# PDU_v1a.net
KiCad netlist of a schematic drawn in EAGLE
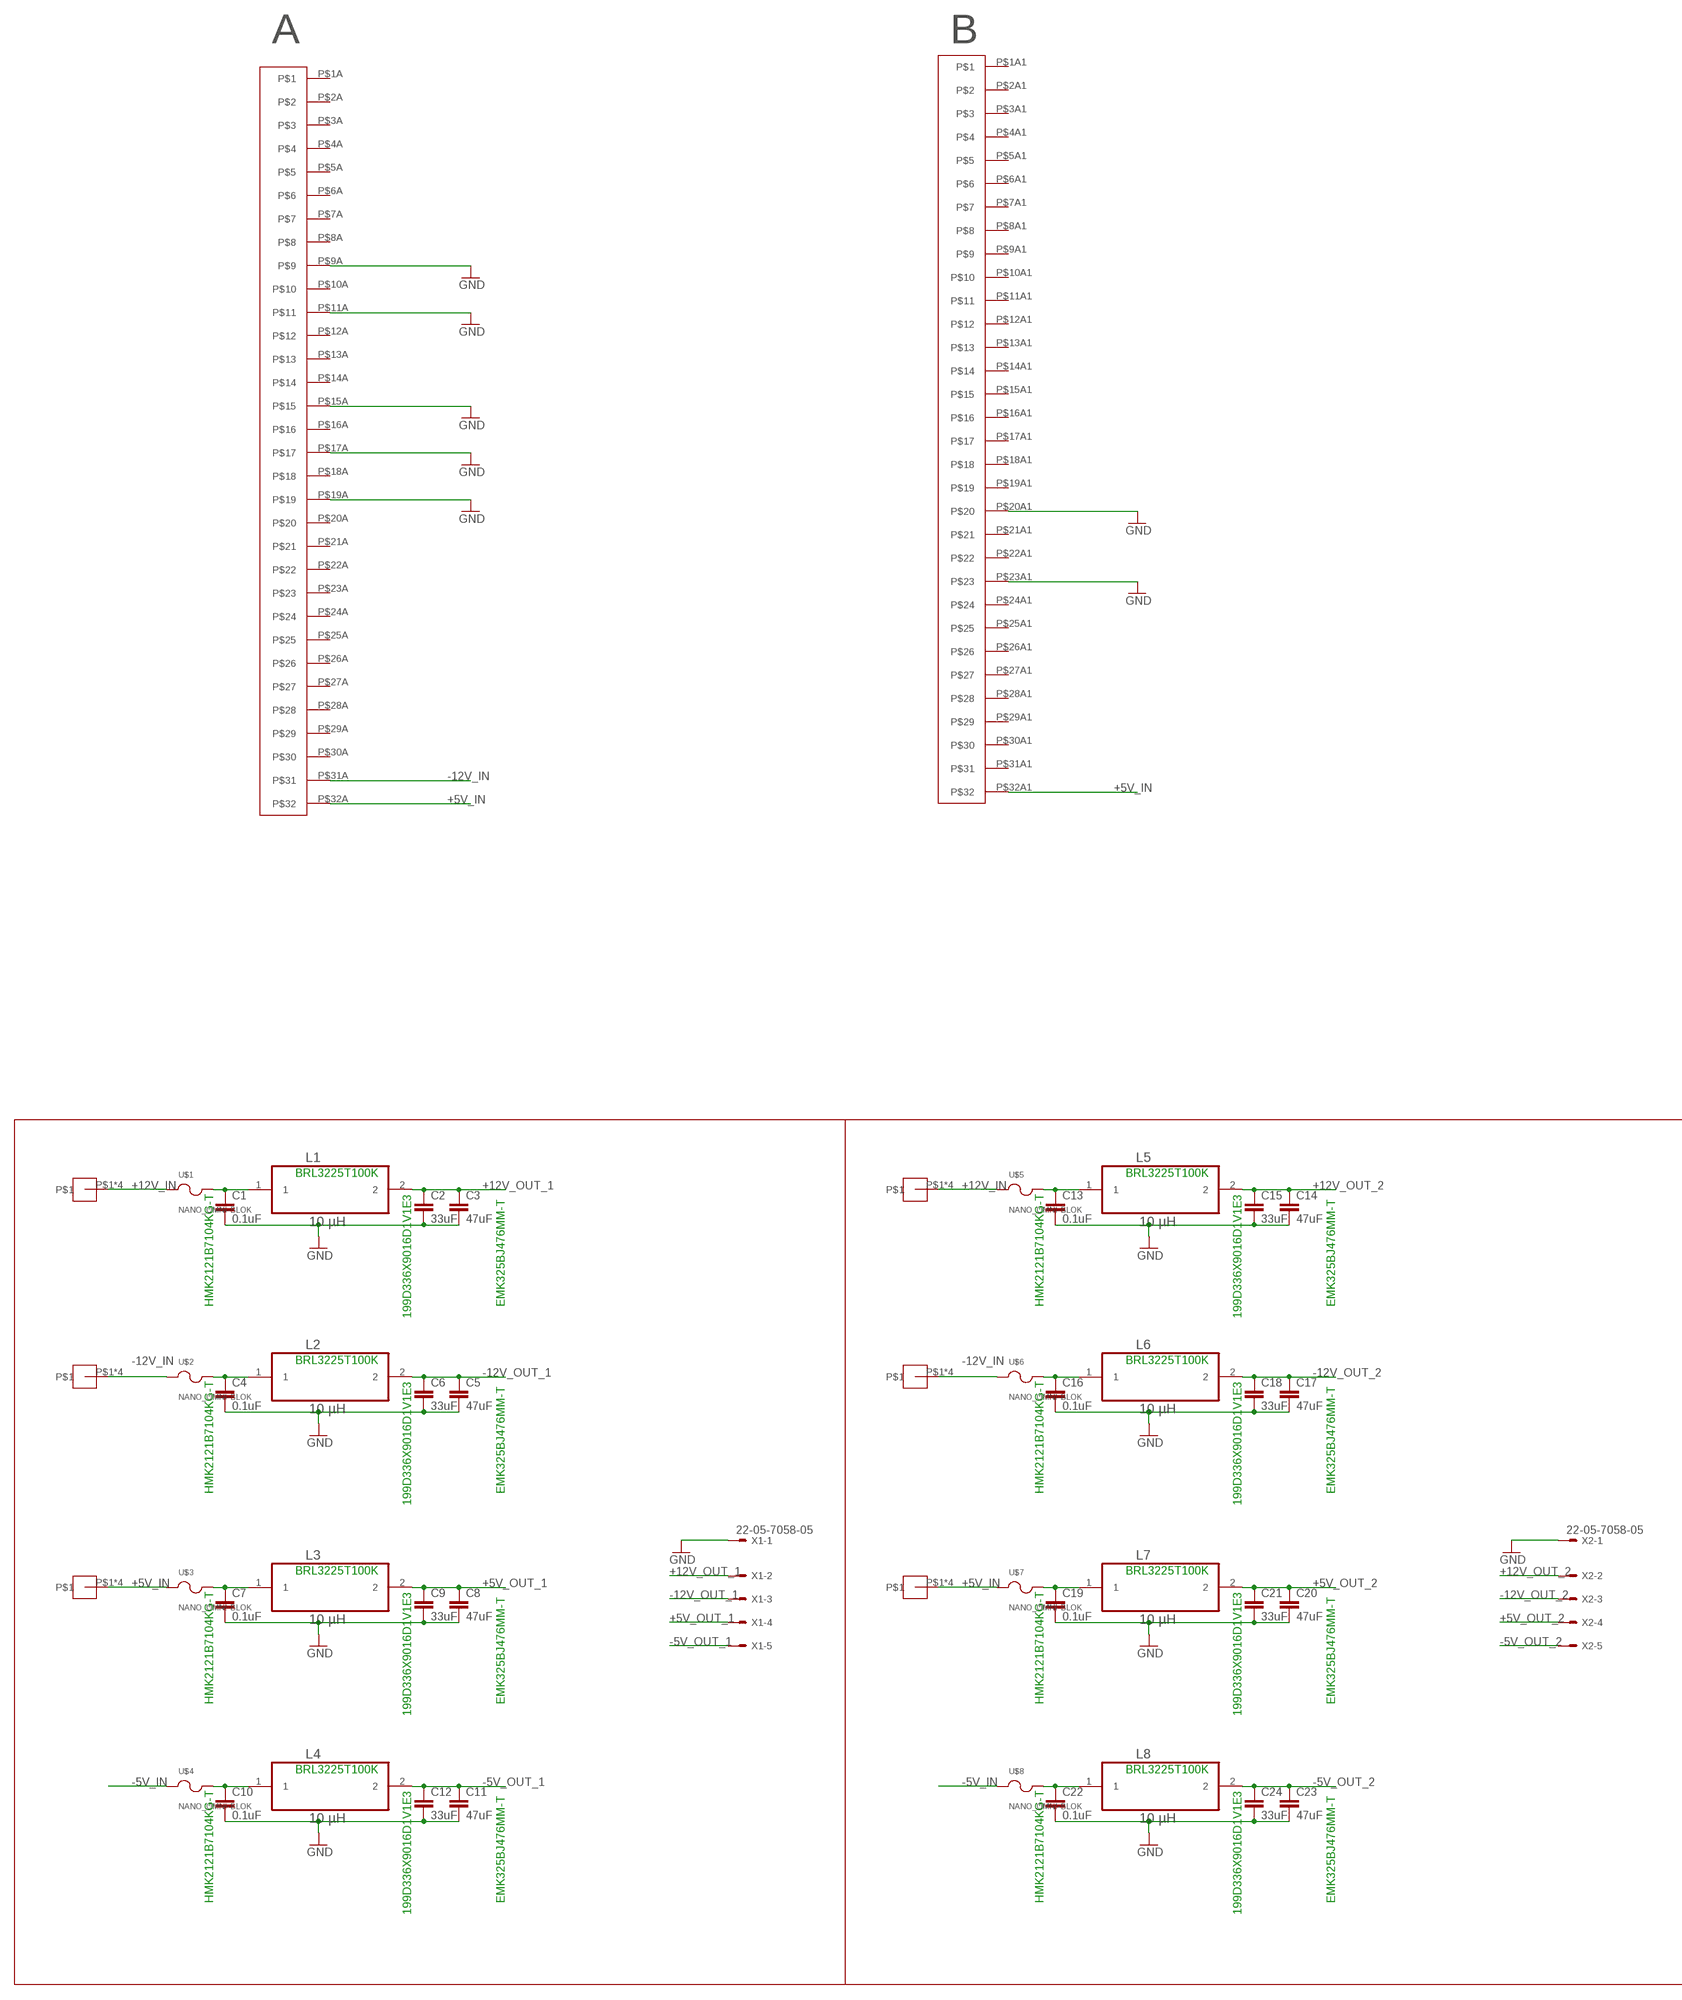
[diagram p0: schematic, sheet 1, part 1 of 2]
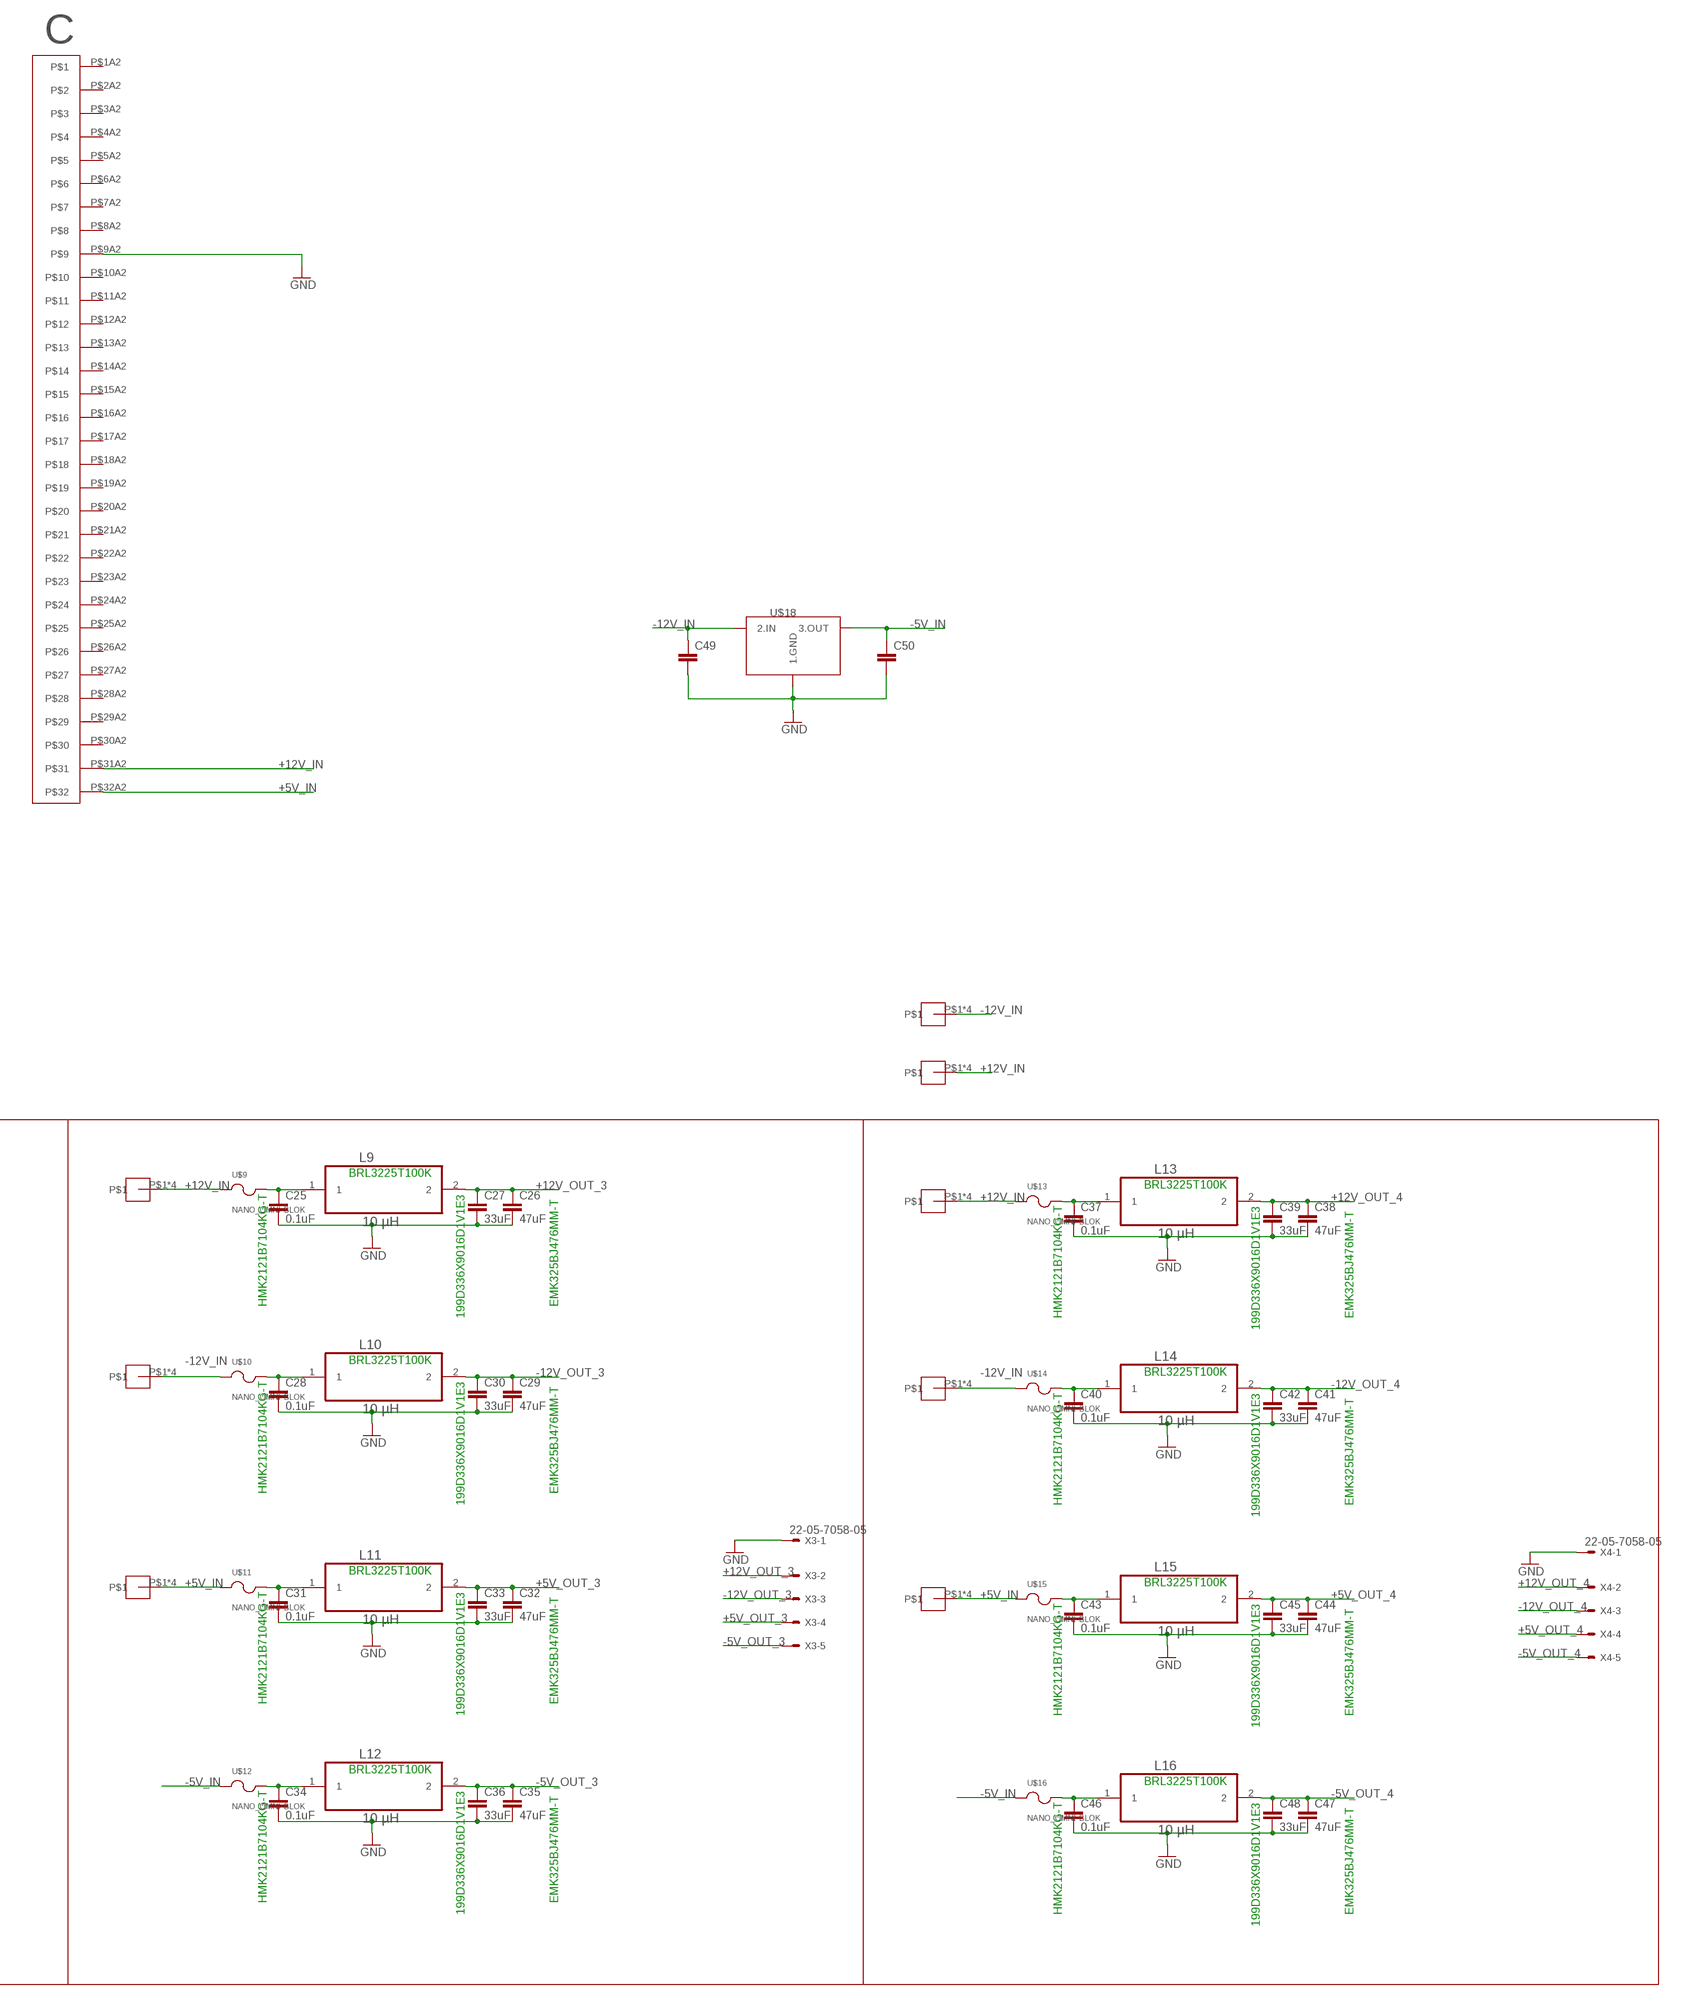
[diagram p1: schematic, sheet 1, part 2 of 2]

(export (version "E")
  (design (tool "Eeschema 10.0.6"))
  (components
    (comp (ref "+5V")
      (value "POWERTAP-7691")
      (footprint "eagle-import:KEYSTONE7691")
      (libsource (lib "eagle-import") (part "POWERTAP-7691"))
    )
    (comp (ref "+5V1")
      (value "POWERTAP-7691")
      (footprint "eagle-import:KEYSTONE7691")
      (libsource (lib "eagle-import") (part "POWERTAP-7691"))
    )
    (comp (ref "+5V2")
      (value "POWERTAP-7691")
      (footprint "eagle-import:KEYSTONE7691")
      (libsource (lib "eagle-import") (part "POWERTAP-7691"))
    )
    (comp (ref "+5V3")
      (value "POWERTAP-7691")
      (footprint "eagle-import:KEYSTONE7691")
      (libsource (lib "eagle-import") (part "POWERTAP-7691"))
    )
    (comp (ref "+12V")
      (value "POWERTAP-7691")
      (footprint "eagle-import:KEYSTONE7691")
      (libsource (lib "eagle-import") (part "POWERTAP-7691"))
    )
    (comp (ref "+12V1")
      (value "POWERTAP-7691")
      (footprint "eagle-import:KEYSTONE7691")
      (libsource (lib "eagle-import") (part "POWERTAP-7691"))
    )
    (comp (ref "+12V2")
      (value "POWERTAP-7691")
      (footprint "eagle-import:KEYSTONE7691")
      (libsource (lib "eagle-import") (part "POWERTAP-7691"))
    )
    (comp (ref "+12V3")
      (value "POWERTAP-7691")
      (footprint "eagle-import:KEYSTONE7691")
      (libsource (lib "eagle-import") (part "POWERTAP-7691"))
    )
    (comp (ref "+12V4")
      (value "POWERTAP-7691")
      (footprint "eagle-import:KEYSTONE7691")
      (libsource (lib "eagle-import") (part "POWERTAP-7691"))
    )
    (comp (ref "-12V")
      (value "POWERTAP-7691")
      (footprint "eagle-import:KEYSTONE7691")
      (libsource (lib "eagle-import") (part "POWERTAP-7691"))
    )
    (comp (ref "-12V1")
      (value "POWERTAP-7691")
      (footprint "eagle-import:KEYSTONE7691")
      (libsource (lib "eagle-import") (part "POWERTAP-7691"))
    )
    (comp (ref "-12V2")
      (value "POWERTAP-7691")
      (footprint "eagle-import:KEYSTONE7691")
      (libsource (lib "eagle-import") (part "POWERTAP-7691"))
    )
    (comp (ref "-12V3")
      (value "POWERTAP-7691")
      (footprint "eagle-import:KEYSTONE7691")
      (libsource (lib "eagle-import") (part "POWERTAP-7691"))
    )
    (comp (ref "-12V4")
      (value "POWERTAP-7691")
      (footprint "eagle-import:KEYSTONE7691")
      (libsource (lib "eagle-import") (part "POWERTAP-7691"))
    )
    (comp (ref "C1")
      (value "0.1uF")
      (footprint "eagle-import:C0805")
      (libsource (lib "eagle-import") (part "C-EUC0805"))
    )
    (comp (ref "C2")
      (value "33uF")
      (footprint "eagle-import:C025-025X050")
      (libsource (lib "eagle-import") (part "C-EU025-025X050"))
    )
    (comp (ref "C3")
      (value "47uF")
      (footprint "eagle-import:C1210")
      (libsource (lib "eagle-import") (part "C-EUC1210"))
    )
    (comp (ref "C4")
      (value "0.1uF")
      (footprint "eagle-import:C0805")
      (libsource (lib "eagle-import") (part "C-EUC0805"))
    )
    (comp (ref "C5")
      (value "47uF")
      (footprint "eagle-import:C1210")
      (libsource (lib "eagle-import") (part "C-EUC1210"))
    )
    (comp (ref "C6")
      (value "33uF")
      (footprint "eagle-import:C025-025X050")
      (libsource (lib "eagle-import") (part "C-EU025-025X050"))
    )
    (comp (ref "C7")
      (value "0.1uF")
      (footprint "eagle-import:C0805")
      (libsource (lib "eagle-import") (part "C-EUC0805"))
    )
    (comp (ref "C8")
      (value "47uF")
      (footprint "eagle-import:C1210")
      (libsource (lib "eagle-import") (part "C-EUC1210"))
    )
    (comp (ref "C9")
      (value "33uF")
      (footprint "eagle-import:C025-025X050")
      (libsource (lib "eagle-import") (part "C-EU025-025X050"))
    )
    (comp (ref "C10")
      (value "0.1uF")
      (footprint "eagle-import:C0805")
      (libsource (lib "eagle-import") (part "C-EUC0805"))
    )
    (comp (ref "C11")
      (value "47uF")
      (footprint "eagle-import:C1210")
      (libsource (lib "eagle-import") (part "C-EUC1210"))
    )
    (comp (ref "C12")
      (value "33uF")
      (footprint "eagle-import:C025-025X050")
      (libsource (lib "eagle-import") (part "C-EU025-025X050"))
    )
    (comp (ref "C13")
      (value "0.1uF")
      (footprint "eagle-import:C0805")
      (libsource (lib "eagle-import") (part "C-EUC0805"))
    )
    (comp (ref "C14")
      (value "47uF")
      (footprint "eagle-import:C1210")
      (libsource (lib "eagle-import") (part "C-EUC1210"))
    )
    (comp (ref "C15")
      (value "33uF")
      (footprint "eagle-import:C025-025X050")
      (libsource (lib "eagle-import") (part "C-EU025-025X050"))
    )
    (comp (ref "C16")
      (value "0.1uF")
      (footprint "eagle-import:C0805")
      (libsource (lib "eagle-import") (part "C-EUC0805"))
    )
    (comp (ref "C17")
      (value "47uF")
      (footprint "eagle-import:C1210")
      (libsource (lib "eagle-import") (part "C-EUC1210"))
    )
    (comp (ref "C18")
      (value "33uF")
      (footprint "eagle-import:C025-025X050")
      (libsource (lib "eagle-import") (part "C-EU025-025X050"))
    )
    (comp (ref "C19")
      (value "0.1uF")
      (footprint "eagle-import:C0805")
      (libsource (lib "eagle-import") (part "C-EUC0805"))
    )
    (comp (ref "C20")
      (value "47uF")
      (footprint "eagle-import:C1210")
      (libsource (lib "eagle-import") (part "C-EUC1210"))
    )
    (comp (ref "C21")
      (value "33uF")
      (footprint "eagle-import:C025-025X050")
      (libsource (lib "eagle-import") (part "C-EU025-025X050"))
    )
    (comp (ref "C22")
      (value "0.1uF")
      (footprint "eagle-import:C0805")
      (libsource (lib "eagle-import") (part "C-EUC0805"))
    )
    (comp (ref "C23")
      (value "47uF")
      (footprint "eagle-import:C1210")
      (libsource (lib "eagle-import") (part "C-EUC1210"))
    )
    (comp (ref "C24")
      (value "33uF")
      (footprint "eagle-import:C025-025X050")
      (libsource (lib "eagle-import") (part "C-EU025-025X050"))
    )
    (comp (ref "C25")
      (value "0.1uF")
      (footprint "eagle-import:C0805")
      (libsource (lib "eagle-import") (part "C-EUC0805"))
    )
    (comp (ref "C26")
      (value "47uF")
      (footprint "eagle-import:C1210")
      (libsource (lib "eagle-import") (part "C-EUC1210"))
    )
    (comp (ref "C27")
      (value "33uF")
      (footprint "eagle-import:C025-025X050")
      (libsource (lib "eagle-import") (part "C-EU025-025X050"))
    )
    (comp (ref "C28")
      (value "0.1uF")
      (footprint "eagle-import:C0805")
      (libsource (lib "eagle-import") (part "C-EUC0805"))
    )
    (comp (ref "C29")
      (value "47uF")
      (footprint "eagle-import:C1210")
      (libsource (lib "eagle-import") (part "C-EUC1210"))
    )
    (comp (ref "C30")
      (value "33uF")
      (footprint "eagle-import:C025-025X050")
      (libsource (lib "eagle-import") (part "C-EU025-025X050"))
    )
    (comp (ref "C31")
      (value "0.1uF")
      (footprint "eagle-import:C0805")
      (libsource (lib "eagle-import") (part "C-EUC0805"))
    )
    (comp (ref "C32")
      (value "47uF")
      (footprint "eagle-import:C1210")
      (libsource (lib "eagle-import") (part "C-EUC1210"))
    )
    (comp (ref "C33")
      (value "33uF")
      (footprint "eagle-import:C025-025X050")
      (libsource (lib "eagle-import") (part "C-EU025-025X050"))
    )
    (comp (ref "C34")
      (value "0.1uF")
      (footprint "eagle-import:C0805")
      (libsource (lib "eagle-import") (part "C-EUC0805"))
    )
    (comp (ref "C35")
      (value "47uF")
      (footprint "eagle-import:C1210")
      (libsource (lib "eagle-import") (part "C-EUC1210"))
    )
    (comp (ref "C36")
      (value "33uF")
      (footprint "eagle-import:C025-025X050")
      (libsource (lib "eagle-import") (part "C-EU025-025X050"))
    )
    (comp (ref "C37")
      (value "0.1uF")
      (footprint "eagle-import:C0805")
      (libsource (lib "eagle-import") (part "C-EUC0805"))
    )
    (comp (ref "C38")
      (value "47uF")
      (footprint "eagle-import:C1210")
      (libsource (lib "eagle-import") (part "C-EUC1210"))
    )
    (comp (ref "C39")
      (value "33uF")
      (footprint "eagle-import:C025-025X050")
      (libsource (lib "eagle-import") (part "C-EU025-025X050"))
    )
    (comp (ref "C40")
      (value "0.1uF")
      (footprint "eagle-import:C0805")
      (libsource (lib "eagle-import") (part "C-EUC0805"))
    )
    (comp (ref "C41")
      (value "47uF")
      (footprint "eagle-import:C1210")
      (libsource (lib "eagle-import") (part "C-EUC1210"))
    )
    (comp (ref "C42")
      (value "33uF")
      (footprint "eagle-import:C025-025X050")
      (libsource (lib "eagle-import") (part "C-EU025-025X050"))
    )
    (comp (ref "C43")
      (value "0.1uF")
      (footprint "eagle-import:C0805")
      (libsource (lib "eagle-import") (part "C-EUC0805"))
    )
    (comp (ref "C44")
      (value "47uF")
      (footprint "eagle-import:C1210")
      (libsource (lib "eagle-import") (part "C-EUC1210"))
    )
    (comp (ref "C45")
      (value "33uF")
      (footprint "eagle-import:C025-025X050")
      (libsource (lib "eagle-import") (part "C-EU025-025X050"))
    )
    (comp (ref "C46")
      (value "0.1uF")
      (footprint "eagle-import:C0805")
      (libsource (lib "eagle-import") (part "C-EUC0805"))
    )
    (comp (ref "C47")
      (value "47uF")
      (footprint "eagle-import:C1210")
      (libsource (lib "eagle-import") (part "C-EUC1210"))
    )
    (comp (ref "C48")
      (value "33uF")
      (footprint "eagle-import:C025-025X050")
      (libsource (lib "eagle-import") (part "C-EU025-025X050"))
    )
    (comp (ref "C49")
      (value "C-EUC0805")
      (footprint "eagle-import:C0805")
      (libsource (lib "eagle-import") (part "C-EUC0805"))
    )
    (comp (ref "C50")
      (value "C-EUC0805")
      (footprint "eagle-import:C0805")
      (libsource (lib "eagle-import") (part "C-EUC0805"))
    )
    (comp (ref "L1")
      (value "10 µH")
      (footprint "eagle-import:INDC3225X240N")
      (fields (field (name "MPN") "B82422H1333K") (field (name "TOLERANCE") "±10%"))
      (libsource (lib "eagle-import") (part "B82422H1333K"))
    )
    (comp (ref "L2")
      (value "10 µH")
      (footprint "eagle-import:INDC3225X240N")
      (fields (field (name "MPN") "B82422H1333K") (field (name "TOLERANCE") "±10%"))
      (libsource (lib "eagle-import") (part "B82422H1333K"))
    )
    (comp (ref "L3")
      (value "10 µH")
      (footprint "eagle-import:INDC3225X240N")
      (fields (field (name "MPN") "B82422H1333K") (field (name "TOLERANCE") "±10%"))
      (libsource (lib "eagle-import") (part "B82422H1333K"))
    )
    (comp (ref "L4")
      (value "10 µH")
      (footprint "eagle-import:INDC3225X240N")
      (fields (field (name "MPN") "B82422H1333K") (field (name "TOLERANCE") "±10%"))
      (libsource (lib "eagle-import") (part "B82422H1333K"))
    )
    (comp (ref "L5")
      (value "10 µH")
      (footprint "eagle-import:INDC3225X240N")
      (fields (field (name "MPN") "B82422H1333K") (field (name "TOLERANCE") "±10%"))
      (libsource (lib "eagle-import") (part "B82422H1333K"))
    )
    (comp (ref "L6")
      (value "10 µH")
      (footprint "eagle-import:INDC3225X240N")
      (fields (field (name "MPN") "B82422H1333K") (field (name "TOLERANCE") "±10%"))
      (libsource (lib "eagle-import") (part "B82422H1333K"))
    )
    (comp (ref "L7")
      (value "10 µH")
      (footprint "eagle-import:INDC3225X240N")
      (fields (field (name "MPN") "B82422H1333K") (field (name "TOLERANCE") "±10%"))
      (libsource (lib "eagle-import") (part "B82422H1333K"))
    )
    (comp (ref "L8")
      (value "10 µH")
      (footprint "eagle-import:INDC3225X240N")
      (fields (field (name "MPN") "B82422H1333K") (field (name "TOLERANCE") "±10%"))
      (libsource (lib "eagle-import") (part "B82422H1333K"))
    )
    (comp (ref "L9")
      (value "10 µH")
      (footprint "eagle-import:INDC3225X240N")
      (fields (field (name "MPN") "B82422H1333K") (field (name "TOLERANCE") "±10%"))
      (libsource (lib "eagle-import") (part "B82422H1333K"))
    )
    (comp (ref "L10")
      (value "10 µH")
      (footprint "eagle-import:INDC3225X240N")
      (fields (field (name "MPN") "B82422H1333K") (field (name "TOLERANCE") "±10%"))
      (libsource (lib "eagle-import") (part "B82422H1333K"))
    )
    (comp (ref "L11")
      (value "10 µH")
      (footprint "eagle-import:INDC3225X240N")
      (fields (field (name "MPN") "B82422H1333K") (field (name "TOLERANCE") "±10%"))
      (libsource (lib "eagle-import") (part "B82422H1333K"))
    )
    (comp (ref "L12")
      (value "10 µH")
      (footprint "eagle-import:INDC3225X240N")
      (fields (field (name "MPN") "B82422H1333K") (field (name "TOLERANCE") "±10%"))
      (libsource (lib "eagle-import") (part "B82422H1333K"))
    )
    (comp (ref "L13")
      (value "10 µH")
      (footprint "eagle-import:INDC3225X240N")
      (fields (field (name "MPN") "B82422H1333K") (field (name "TOLERANCE") "±10%"))
      (libsource (lib "eagle-import") (part "B82422H1333K"))
    )
    (comp (ref "L14")
      (value "10 µH")
      (footprint "eagle-import:INDC3225X240N")
      (fields (field (name "MPN") "B82422H1333K") (field (name "TOLERANCE") "±10%"))
      (libsource (lib "eagle-import") (part "B82422H1333K"))
    )
    (comp (ref "L15")
      (value "10 µH")
      (footprint "eagle-import:INDC3225X240N")
      (fields (field (name "MPN") "B82422H1333K") (field (name "TOLERANCE") "±10%"))
      (libsource (lib "eagle-import") (part "B82422H1333K"))
    )
    (comp (ref "L16")
      (value "10 µH")
      (footprint "eagle-import:INDC3225X240N")
      (fields (field (name "MPN") "B82422H1333K") (field (name "TOLERANCE") "±10%"))
      (libsource (lib "eagle-import") (part "B82422H1333K"))
    )
    (comp (ref "U$1")
      (value "NANO_OMNI-BLOK")
      (footprint "eagle-import:NANO2-OMNI-BLOK")
      (libsource (lib "eagle-import") (part "NANO_OMNI-BLOK"))
    )
    (comp (ref "U$2")
      (value "NANO_OMNI-BLOK")
      (footprint "eagle-import:NANO2-OMNI-BLOK")
      (libsource (lib "eagle-import") (part "NANO_OMNI-BLOK"))
    )
    (comp (ref "U$3")
      (value "NANO_OMNI-BLOK")
      (footprint "eagle-import:NANO2-OMNI-BLOK")
      (libsource (lib "eagle-import") (part "NANO_OMNI-BLOK"))
    )
    (comp (ref "U$4")
      (value "NANO_OMNI-BLOK")
      (footprint "eagle-import:NANO2-OMNI-BLOK")
      (libsource (lib "eagle-import") (part "NANO_OMNI-BLOK"))
    )
    (comp (ref "U$5")
      (value "NANO_OMNI-BLOK")
      (footprint "eagle-import:NANO2-OMNI-BLOK")
      (libsource (lib "eagle-import") (part "NANO_OMNI-BLOK"))
    )
    (comp (ref "U$6")
      (value "NANO_OMNI-BLOK")
      (footprint "eagle-import:NANO2-OMNI-BLOK")
      (libsource (lib "eagle-import") (part "NANO_OMNI-BLOK"))
    )
    (comp (ref "U$7")
      (value "NANO_OMNI-BLOK")
      (footprint "eagle-import:NANO2-OMNI-BLOK")
      (libsource (lib "eagle-import") (part "NANO_OMNI-BLOK"))
    )
    (comp (ref "U$8")
      (value "NANO_OMNI-BLOK")
      (footprint "eagle-import:NANO2-OMNI-BLOK")
      (libsource (lib "eagle-import") (part "NANO_OMNI-BLOK"))
    )
    (comp (ref "U$9")
      (value "NANO_OMNI-BLOK")
      (footprint "eagle-import:NANO2-OMNI-BLOK")
      (libsource (lib "eagle-import") (part "NANO_OMNI-BLOK"))
    )
    (comp (ref "U$10")
      (value "NANO_OMNI-BLOK")
      (footprint "eagle-import:NANO2-OMNI-BLOK")
      (libsource (lib "eagle-import") (part "NANO_OMNI-BLOK"))
    )
    (comp (ref "U$11")
      (value "NANO_OMNI-BLOK")
      (footprint "eagle-import:NANO2-OMNI-BLOK")
      (libsource (lib "eagle-import") (part "NANO_OMNI-BLOK"))
    )
    (comp (ref "U$12")
      (value "NANO_OMNI-BLOK")
      (footprint "eagle-import:NANO2-OMNI-BLOK")
      (libsource (lib "eagle-import") (part "NANO_OMNI-BLOK"))
    )
    (comp (ref "U$13")
      (value "NANO_OMNI-BLOK")
      (footprint "eagle-import:NANO2-OMNI-BLOK")
      (libsource (lib "eagle-import") (part "NANO_OMNI-BLOK"))
    )
    (comp (ref "U$14")
      (value "NANO_OMNI-BLOK")
      (footprint "eagle-import:NANO2-OMNI-BLOK")
      (libsource (lib "eagle-import") (part "NANO_OMNI-BLOK"))
    )
    (comp (ref "U$15")
      (value "NANO_OMNI-BLOK")
      (footprint "eagle-import:NANO2-OMNI-BLOK")
      (libsource (lib "eagle-import") (part "NANO_OMNI-BLOK"))
    )
    (comp (ref "U$16")
      (value "NANO_OMNI-BLOK")
      (footprint "eagle-import:NANO2-OMNI-BLOK")
      (libsource (lib "eagle-import") (part "NANO_OMNI-BLOK"))
    )
    (comp (ref "U$17")
      (value "DIN_41612_PLUG")
      (footprint "eagle-import:DIN_41612_PLUG")
      (libsource (lib "eagle-import") (part "DIN_41612_PLUG"))
    )
    (comp (ref "U$18")
      (value "LM2990")
      (footprint "eagle-import:TO-263-3")
      (libsource (lib "eagle-import") (part "LM2990"))
    )
    (comp (ref "X1")
      (value "22-05-7058-05")
      (footprint "eagle-import:7395-05")
      (libsource (lib "eagle-import") (part "22-?-0505-7058"))
    )
    (comp (ref "X2")
      (value "22-05-7058-05")
      (footprint "eagle-import:7395-05")
      (libsource (lib "eagle-import") (part "22-?-0505-7058"))
    )
    (comp (ref "X3")
      (value "22-05-7058-05")
      (footprint "eagle-import:7395-05")
      (libsource (lib "eagle-import") (part "22-?-0505-7058"))
    )
    (comp (ref "X4")
      (value "22-05-7058-05")
      (footprint "eagle-import:7395-05")
      (libsource (lib "eagle-import") (part "22-?-0505-7058"))
    )
  )
  (nets
    (net (code "1") (name "+5V_IN") (class "Default")
      (node (ref "+5V") (pin "P$1") (pinfunction "P$1_P$1") (pintype "bidirectional"))
      (node (ref "+5V") (pin "P$2") (pinfunction "P$1_P$2") (pintype "bidirectional"))
      (node (ref "+5V") (pin "P$3") (pinfunction "P$1_P$3") (pintype "bidirectional"))
      (node (ref "+5V") (pin "P$4") (pinfunction "P$1_P$4") (pintype "bidirectional"))
      (node (ref "+5V1") (pin "P$1") (pinfunction "P$1_P$1") (pintype "bidirectional"))
      (node (ref "+5V1") (pin "P$2") (pinfunction "P$1_P$2") (pintype "bidirectional"))
      (node (ref "+5V1") (pin "P$3") (pinfunction "P$1_P$3") (pintype "bidirectional"))
      (node (ref "+5V1") (pin "P$4") (pinfunction "P$1_P$4") (pintype "bidirectional"))
      (node (ref "+5V2") (pin "P$1") (pinfunction "P$1_P$1") (pintype "bidirectional"))
      (node (ref "+5V2") (pin "P$2") (pinfunction "P$1_P$2") (pintype "bidirectional"))
      (node (ref "+5V2") (pin "P$3") (pinfunction "P$1_P$3") (pintype "bidirectional"))
      (node (ref "+5V2") (pin "P$4") (pinfunction "P$1_P$4") (pintype "bidirectional"))
      (node (ref "+5V3") (pin "P$1") (pinfunction "P$1_P$1") (pintype "bidirectional"))
      (node (ref "+5V3") (pin "P$2") (pinfunction "P$1_P$2") (pintype "bidirectional"))
      (node (ref "+5V3") (pin "P$3") (pinfunction "P$1_P$3") (pintype "bidirectional"))
      (node (ref "+5V3") (pin "P$4") (pinfunction "P$1_P$4") (pintype "bidirectional"))
      (node (ref "U$11") (pin "P$1") (pinfunction "P$1_P$1") (pintype "bidirectional"))
      (node (ref "U$15") (pin "P$1") (pinfunction "P$1_P$1") (pintype "bidirectional"))
      (node (ref "U$17") (pin "P$32A") (pinfunction "P$32_P$32A") (pintype "bidirectional"))
      (node (ref "U$17") (pin "P$32A1") (pinfunction "P$32_P$32A1") (pintype "bidirectional"))
      (node (ref "U$17") (pin "P$32A2") (pinfunction "P$32_P$32A2") (pintype "bidirectional"))
      (node (ref "U$3") (pin "P$1") (pinfunction "P$1_P$1") (pintype "bidirectional"))
      (node (ref "U$7") (pin "P$1") (pinfunction "P$1_P$1") (pintype "bidirectional"))
    )
    (net (code "2") (name "+5V_OUT_1") (class "Default")
      (node (ref "C8") (pin "1") (pinfunction "1_1") (pintype "passive"))
      (node (ref "C9") (pin "1") (pinfunction "1_1") (pintype "passive"))
      (node (ref "L3") (pin "2") (pinfunction "2_2") (pintype "passive"))
      (node (ref "X1") (pin "4") (pinfunction "S_4") (pintype "passive"))
    )
    (net (code "3") (name "+5V_OUT_2") (class "Default")
      (node (ref "C20") (pin "1") (pinfunction "1_1") (pintype "passive"))
      (node (ref "C21") (pin "1") (pinfunction "1_1") (pintype "passive"))
      (node (ref "L7") (pin "2") (pinfunction "2_2") (pintype "passive"))
      (node (ref "X2") (pin "4") (pinfunction "S_4") (pintype "passive"))
    )
    (net (code "4") (name "+5V_OUT_3") (class "Default")
      (node (ref "C32") (pin "1") (pinfunction "1_1") (pintype "passive"))
      (node (ref "C33") (pin "1") (pinfunction "1_1") (pintype "passive"))
      (node (ref "L11") (pin "2") (pinfunction "2_2") (pintype "passive"))
      (node (ref "X3") (pin "4") (pinfunction "S_4") (pintype "passive"))
    )
    (net (code "5") (name "+5V_OUT_4") (class "Default")
      (node (ref "C44") (pin "1") (pinfunction "1_1") (pintype "passive"))
      (node (ref "C45") (pin "1") (pinfunction "1_1") (pintype "passive"))
      (node (ref "L15") (pin "2") (pinfunction "2_2") (pintype "passive"))
      (node (ref "X4") (pin "4") (pinfunction "S_4") (pintype "passive"))
    )
    (net (code "6") (name "+12V_IN") (class "Default")
      (node (ref "+12V") (pin "P$1") (pinfunction "P$1_P$1") (pintype "bidirectional"))
      (node (ref "+12V") (pin "P$2") (pinfunction "P$1_P$2") (pintype "bidirectional"))
      (node (ref "+12V") (pin "P$3") (pinfunction "P$1_P$3") (pintype "bidirectional"))
      (node (ref "+12V") (pin "P$4") (pinfunction "P$1_P$4") (pintype "bidirectional"))
      (node (ref "+12V1") (pin "P$1") (pinfunction "P$1_P$1") (pintype "bidirectional"))
      (node (ref "+12V1") (pin "P$2") (pinfunction "P$1_P$2") (pintype "bidirectional"))
      (node (ref "+12V1") (pin "P$3") (pinfunction "P$1_P$3") (pintype "bidirectional"))
      (node (ref "+12V1") (pin "P$4") (pinfunction "P$1_P$4") (pintype "bidirectional"))
      (node (ref "+12V2") (pin "P$1") (pinfunction "P$1_P$1") (pintype "bidirectional"))
      (node (ref "+12V2") (pin "P$2") (pinfunction "P$1_P$2") (pintype "bidirectional"))
      (node (ref "+12V2") (pin "P$3") (pinfunction "P$1_P$3") (pintype "bidirectional"))
      (node (ref "+12V2") (pin "P$4") (pinfunction "P$1_P$4") (pintype "bidirectional"))
      (node (ref "+12V3") (pin "P$1") (pinfunction "P$1_P$1") (pintype "bidirectional"))
      (node (ref "+12V3") (pin "P$2") (pinfunction "P$1_P$2") (pintype "bidirectional"))
      (node (ref "+12V3") (pin "P$3") (pinfunction "P$1_P$3") (pintype "bidirectional"))
      (node (ref "+12V3") (pin "P$4") (pinfunction "P$1_P$4") (pintype "bidirectional"))
      (node (ref "+12V4") (pin "P$1") (pinfunction "P$1_P$1") (pintype "bidirectional"))
      (node (ref "+12V4") (pin "P$2") (pinfunction "P$1_P$2") (pintype "bidirectional"))
      (node (ref "+12V4") (pin "P$3") (pinfunction "P$1_P$3") (pintype "bidirectional"))
      (node (ref "+12V4") (pin "P$4") (pinfunction "P$1_P$4") (pintype "bidirectional"))
      (node (ref "U$1") (pin "P$1") (pinfunction "P$1_P$1") (pintype "bidirectional"))
      (node (ref "U$13") (pin "P$1") (pinfunction "P$1_P$1") (pintype "bidirectional"))
      (node (ref "U$17") (pin "P$31A2") (pinfunction "P$31_P$31A2") (pintype "bidirectional"))
      (node (ref "U$5") (pin "P$1") (pinfunction "P$1_P$1") (pintype "bidirectional"))
      (node (ref "U$9") (pin "P$1") (pinfunction "P$1_P$1") (pintype "bidirectional"))
    )
    (net (code "7") (name "+12V_OUT_1") (class "Default")
      (node (ref "C2") (pin "1") (pinfunction "1_1") (pintype "passive"))
      (node (ref "C3") (pin "1") (pinfunction "1_1") (pintype "passive"))
      (node (ref "L1") (pin "2") (pinfunction "2_2") (pintype "passive"))
      (node (ref "X1") (pin "2") (pinfunction "S_2") (pintype "passive"))
    )
    (net (code "8") (name "+12V_OUT_2") (class "Default")
      (node (ref "C14") (pin "1") (pinfunction "1_1") (pintype "passive"))
      (node (ref "C15") (pin "1") (pinfunction "1_1") (pintype "passive"))
      (node (ref "L5") (pin "2") (pinfunction "2_2") (pintype "passive"))
      (node (ref "X2") (pin "2") (pinfunction "S_2") (pintype "passive"))
    )
    (net (code "9") (name "+12V_OUT_3") (class "Default")
      (node (ref "C26") (pin "1") (pinfunction "1_1") (pintype "passive"))
      (node (ref "C27") (pin "1") (pinfunction "1_1") (pintype "passive"))
      (node (ref "L9") (pin "2") (pinfunction "2_2") (pintype "passive"))
      (node (ref "X3") (pin "2") (pinfunction "S_2") (pintype "passive"))
    )
    (net (code "10") (name "+12V_OUT_4") (class "Default")
      (node (ref "C38") (pin "1") (pinfunction "1_1") (pintype "passive"))
      (node (ref "C39") (pin "1") (pinfunction "1_1") (pintype "passive"))
      (node (ref "L13") (pin "2") (pinfunction "2_2") (pintype "passive"))
      (node (ref "X4") (pin "2") (pinfunction "S_2") (pintype "passive"))
    )
    (net (code "11") (name "-5V_IN") (class "Default")
      (node (ref "C50") (pin "1") (pinfunction "1_1") (pintype "passive"))
      (node (ref "U$12") (pin "P$1") (pinfunction "P$1_P$1") (pintype "bidirectional"))
      (node (ref "U$16") (pin "P$1") (pinfunction "P$1_P$1") (pintype "bidirectional"))
      (node (ref "U$18") (pin "P$3") (pinfunction "3.OUT_P$3") (pintype "bidirectional"))
      (node (ref "U$4") (pin "P$1") (pinfunction "P$1_P$1") (pintype "bidirectional"))
      (node (ref "U$8") (pin "P$1") (pinfunction "P$1_P$1") (pintype "bidirectional"))
    )
    (net (code "12") (name "-5V_OUT_1") (class "Default")
      (node (ref "C11") (pin "1") (pinfunction "1_1") (pintype "passive"))
      (node (ref "C12") (pin "1") (pinfunction "1_1") (pintype "passive"))
      (node (ref "L4") (pin "2") (pinfunction "2_2") (pintype "passive"))
      (node (ref "X1") (pin "5") (pinfunction "S_5") (pintype "passive"))
    )
    (net (code "13") (name "-5V_OUT_2") (class "Default")
      (node (ref "C23") (pin "1") (pinfunction "1_1") (pintype "passive"))
      (node (ref "C24") (pin "1") (pinfunction "1_1") (pintype "passive"))
      (node (ref "L8") (pin "2") (pinfunction "2_2") (pintype "passive"))
      (node (ref "X2") (pin "5") (pinfunction "S_5") (pintype "passive"))
    )
    (net (code "14") (name "-5V_OUT_3") (class "Default")
      (node (ref "C35") (pin "1") (pinfunction "1_1") (pintype "passive"))
      (node (ref "C36") (pin "1") (pinfunction "1_1") (pintype "passive"))
      (node (ref "L12") (pin "2") (pinfunction "2_2") (pintype "passive"))
      (node (ref "X3") (pin "5") (pinfunction "S_5") (pintype "passive"))
    )
    (net (code "15") (name "-5V_OUT_4") (class "Default")
      (node (ref "C47") (pin "1") (pinfunction "1_1") (pintype "passive"))
      (node (ref "C48") (pin "1") (pinfunction "1_1") (pintype "passive"))
      (node (ref "L16") (pin "2") (pinfunction "2_2") (pintype "passive"))
      (node (ref "X4") (pin "5") (pinfunction "S_5") (pintype "passive"))
    )
    (net (code "16") (name "-12V_IN") (class "Default")
      (node (ref "-12V") (pin "P$1") (pinfunction "P$1_P$1") (pintype "bidirectional"))
      (node (ref "-12V") (pin "P$2") (pinfunction "P$1_P$2") (pintype "bidirectional"))
      (node (ref "-12V") (pin "P$3") (pinfunction "P$1_P$3") (pintype "bidirectional"))
      (node (ref "-12V") (pin "P$4") (pinfunction "P$1_P$4") (pintype "bidirectional"))
      (node (ref "-12V1") (pin "P$1") (pinfunction "P$1_P$1") (pintype "bidirectional"))
      (node (ref "-12V1") (pin "P$2") (pinfunction "P$1_P$2") (pintype "bidirectional"))
      (node (ref "-12V1") (pin "P$3") (pinfunction "P$1_P$3") (pintype "bidirectional"))
      (node (ref "-12V1") (pin "P$4") (pinfunction "P$1_P$4") (pintype "bidirectional"))
      (node (ref "-12V2") (pin "P$1") (pinfunction "P$1_P$1") (pintype "bidirectional"))
      (node (ref "-12V2") (pin "P$2") (pinfunction "P$1_P$2") (pintype "bidirectional"))
      (node (ref "-12V2") (pin "P$3") (pinfunction "P$1_P$3") (pintype "bidirectional"))
      (node (ref "-12V2") (pin "P$4") (pinfunction "P$1_P$4") (pintype "bidirectional"))
      (node (ref "-12V3") (pin "P$1") (pinfunction "P$1_P$1") (pintype "bidirectional"))
      (node (ref "-12V3") (pin "P$2") (pinfunction "P$1_P$2") (pintype "bidirectional"))
      (node (ref "-12V3") (pin "P$3") (pinfunction "P$1_P$3") (pintype "bidirectional"))
      (node (ref "-12V3") (pin "P$4") (pinfunction "P$1_P$4") (pintype "bidirectional"))
      (node (ref "-12V4") (pin "P$1") (pinfunction "P$1_P$1") (pintype "bidirectional"))
      (node (ref "-12V4") (pin "P$2") (pinfunction "P$1_P$2") (pintype "bidirectional"))
      (node (ref "-12V4") (pin "P$3") (pinfunction "P$1_P$3") (pintype "bidirectional"))
      (node (ref "-12V4") (pin "P$4") (pinfunction "P$1_P$4") (pintype "bidirectional"))
      (node (ref "C49") (pin "1") (pinfunction "1_1") (pintype "passive"))
      (node (ref "U$10") (pin "P$1") (pinfunction "P$1_P$1") (pintype "bidirectional"))
      (node (ref "U$14") (pin "P$1") (pinfunction "P$1_P$1") (pintype "bidirectional"))
      (node (ref "U$17") (pin "P$31A") (pinfunction "P$31_P$31A") (pintype "bidirectional"))
      (node (ref "U$18") (pin "P$2") (pinfunction "2.IN_P$2") (pintype "bidirectional"))
      (node (ref "U$18") (pin "P$4") (pinfunction "2.IN_P$4") (pintype "bidirectional"))
      (node (ref "U$2") (pin "P$1") (pinfunction "P$1_P$1") (pintype "bidirectional"))
      (node (ref "U$6") (pin "P$1") (pinfunction "P$1_P$1") (pintype "bidirectional"))
    )
    (net (code "17") (name "-12V_OUT_1") (class "Default")
      (node (ref "C5") (pin "1") (pinfunction "1_1") (pintype "passive"))
      (node (ref "C6") (pin "1") (pinfunction "1_1") (pintype "passive"))
      (node (ref "L2") (pin "2") (pinfunction "2_2") (pintype "passive"))
      (node (ref "X1") (pin "3") (pinfunction "S_3") (pintype "passive"))
    )
    (net (code "18") (name "-12V_OUT_2") (class "Default")
      (node (ref "C17") (pin "1") (pinfunction "1_1") (pintype "passive"))
      (node (ref "C18") (pin "1") (pinfunction "1_1") (pintype "passive"))
      (node (ref "L6") (pin "2") (pinfunction "2_2") (pintype "passive"))
      (node (ref "X2") (pin "3") (pinfunction "S_3") (pintype "passive"))
    )
    (net (code "19") (name "-12V_OUT_3") (class "Default")
      (node (ref "C29") (pin "1") (pinfunction "1_1") (pintype "passive"))
      (node (ref "C30") (pin "1") (pinfunction "1_1") (pintype "passive"))
      (node (ref "L10") (pin "2") (pinfunction "2_2") (pintype "passive"))
      (node (ref "X3") (pin "3") (pinfunction "S_3") (pintype "passive"))
    )
    (net (code "20") (name "-12V_OUT_4") (class "Default")
      (node (ref "C41") (pin "1") (pinfunction "1_1") (pintype "passive"))
      (node (ref "C42") (pin "1") (pinfunction "1_1") (pintype "passive"))
      (node (ref "L14") (pin "2") (pinfunction "2_2") (pintype "passive"))
      (node (ref "X4") (pin "3") (pinfunction "S_3") (pintype "passive"))
    )
    (net (code "21") (name "GND") (class "Default")
      (node (ref "C1") (pin "2") (pinfunction "2_2") (pintype "passive"))
      (node (ref "C10") (pin "2") (pinfunction "2_2") (pintype "passive"))
      (node (ref "C11") (pin "2") (pinfunction "2_2") (pintype "passive"))
      (node (ref "C12") (pin "2") (pinfunction "2_2") (pintype "passive"))
      (node (ref "C13") (pin "2") (pinfunction "2_2") (pintype "passive"))
      (node (ref "C14") (pin "2") (pinfunction "2_2") (pintype "passive"))
      (node (ref "C15") (pin "2") (pinfunction "2_2") (pintype "passive"))
      (node (ref "C16") (pin "2") (pinfunction "2_2") (pintype "passive"))
      (node (ref "C17") (pin "2") (pinfunction "2_2") (pintype "passive"))
      (node (ref "C18") (pin "2") (pinfunction "2_2") (pintype "passive"))
      (node (ref "C19") (pin "2") (pinfunction "2_2") (pintype "passive"))
      (node (ref "C2") (pin "2") (pinfunction "2_2") (pintype "passive"))
      (node (ref "C20") (pin "2") (pinfunction "2_2") (pintype "passive"))
      (node (ref "C21") (pin "2") (pinfunction "2_2") (pintype "passive"))
      (node (ref "C22") (pin "2") (pinfunction "2_2") (pintype "passive"))
      (node (ref "C23") (pin "2") (pinfunction "2_2") (pintype "passive"))
      (node (ref "C24") (pin "2") (pinfunction "2_2") (pintype "passive"))
      (node (ref "C25") (pin "2") (pinfunction "2_2") (pintype "passive"))
      (node (ref "C26") (pin "2") (pinfunction "2_2") (pintype "passive"))
      (node (ref "C27") (pin "2") (pinfunction "2_2") (pintype "passive"))
      (node (ref "C28") (pin "2") (pinfunction "2_2") (pintype "passive"))
      (node (ref "C29") (pin "2") (pinfunction "2_2") (pintype "passive"))
      (node (ref "C3") (pin "2") (pinfunction "2_2") (pintype "passive"))
      (node (ref "C30") (pin "2") (pinfunction "2_2") (pintype "passive"))
      (node (ref "C31") (pin "2") (pinfunction "2_2") (pintype "passive"))
      (node (ref "C32") (pin "2") (pinfunction "2_2") (pintype "passive"))
      (node (ref "C33") (pin "2") (pinfunction "2_2") (pintype "passive"))
      (node (ref "C34") (pin "2") (pinfunction "2_2") (pintype "passive"))
      (node (ref "C35") (pin "2") (pinfunction "2_2") (pintype "passive"))
      (node (ref "C36") (pin "2") (pinfunction "2_2") (pintype "passive"))
      (node (ref "C37") (pin "2") (pinfunction "2_2") (pintype "passive"))
      (node (ref "C38") (pin "2") (pinfunction "2_2") (pintype "passive"))
      (node (ref "C39") (pin "2") (pinfunction "2_2") (pintype "passive"))
      (node (ref "C4") (pin "2") (pinfunction "2_2") (pintype "passive"))
      (node (ref "C40") (pin "2") (pinfunction "2_2") (pintype "passive"))
      (node (ref "C41") (pin "2") (pinfunction "2_2") (pintype "passive"))
      (node (ref "C42") (pin "2") (pinfunction "2_2") (pintype "passive"))
      (node (ref "C43") (pin "2") (pinfunction "2_2") (pintype "passive"))
      (node (ref "C44") (pin "2") (pinfunction "2_2") (pintype "passive"))
      (node (ref "C45") (pin "2") (pinfunction "2_2") (pintype "passive"))
      (node (ref "C46") (pin "2") (pinfunction "2_2") (pintype "passive"))
      (node (ref "C47") (pin "2") (pinfunction "2_2") (pintype "passive"))
      (node (ref "C48") (pin "2") (pinfunction "2_2") (pintype "passive"))
      (node (ref "C49") (pin "2") (pinfunction "2_2") (pintype "passive"))
      (node (ref "C5") (pin "2") (pinfunction "2_2") (pintype "passive"))
      (node (ref "C50") (pin "2") (pinfunction "2_2") (pintype "passive"))
      (node (ref "C6") (pin "2") (pinfunction "2_2") (pintype "passive"))
      (node (ref "C7") (pin "2") (pinfunction "2_2") (pintype "passive"))
      (node (ref "C8") (pin "2") (pinfunction "2_2") (pintype "passive"))
      (node (ref "C9") (pin "2") (pinfunction "2_2") (pintype "passive"))
      (node (ref "U$17") (pin "P$11A") (pinfunction "P$11_P$11A") (pintype "bidirectional"))
      (node (ref "U$17") (pin "P$15A") (pinfunction "P$15_P$15A") (pintype "bidirectional"))
      (node (ref "U$17") (pin "P$17A") (pinfunction "P$17_P$17A") (pintype "bidirectional"))
      (node (ref "U$17") (pin "P$19A") (pinfunction "P$19_P$19A") (pintype "bidirectional"))
      (node (ref "U$17") (pin "P$20A1") (pinfunction "P$20_P$20A1") (pintype "bidirectional"))
      (node (ref "U$17") (pin "P$23A1") (pinfunction "P$23_P$23A1") (pintype "bidirectional"))
      (node (ref "U$17") (pin "P$9A") (pinfunction "P$9_P$9A") (pintype "bidirectional"))
      (node (ref "U$17") (pin "P$9A2") (pinfunction "P$9_P$9A2") (pintype "bidirectional"))
      (node (ref "U$18") (pin "P$1") (pinfunction "1.GND_P$1") (pintype "bidirectional"))
      (node (ref "X1") (pin "1") (pinfunction "S_1") (pintype "passive"))
      (node (ref "X2") (pin "1") (pinfunction "S_1") (pintype "passive"))
      (node (ref "X3") (pin "1") (pinfunction "S_1") (pintype "passive"))
      (node (ref "X4") (pin "1") (pinfunction "S_1") (pintype "passive"))
    )
    (net (code "22") (name "Net-(C1-Pad1)") (class "Default")
      (node (ref "C1") (pin "1") (pinfunction "1_1") (pintype "passive"))
      (node (ref "L1") (pin "1") (pinfunction "1_1") (pintype "passive"))
      (node (ref "U$1") (pin "P$2") (pinfunction "P$2_P$2") (pintype "bidirectional"))
    )
    (net (code "23") (name "Net-(C4-Pad1)") (class "Default")
      (node (ref "C4") (pin "1") (pinfunction "1_1") (pintype "passive"))
      (node (ref "L2") (pin "1") (pinfunction "1_1") (pintype "passive"))
      (node (ref "U$2") (pin "P$2") (pinfunction "P$2_P$2") (pintype "bidirectional"))
    )
    (net (code "24") (name "Net-(C7-Pad1)") (class "Default")
      (node (ref "C7") (pin "1") (pinfunction "1_1") (pintype "passive"))
      (node (ref "L3") (pin "1") (pinfunction "1_1") (pintype "passive"))
      (node (ref "U$3") (pin "P$2") (pinfunction "P$2_P$2") (pintype "bidirectional"))
    )
    (net (code "25") (name "Net-(C10-Pad1)") (class "Default")
      (node (ref "C10") (pin "1") (pinfunction "1_1") (pintype "passive"))
      (node (ref "L4") (pin "1") (pinfunction "1_1") (pintype "passive"))
      (node (ref "U$4") (pin "P$2") (pinfunction "P$2_P$2") (pintype "bidirectional"))
    )
    (net (code "26") (name "Net-(C13-Pad1)") (class "Default")
      (node (ref "C13") (pin "1") (pinfunction "1_1") (pintype "passive"))
      (node (ref "L5") (pin "1") (pinfunction "1_1") (pintype "passive"))
      (node (ref "U$5") (pin "P$2") (pinfunction "P$2_P$2") (pintype "bidirectional"))
    )
    (net (code "27") (name "Net-(C16-Pad1)") (class "Default")
      (node (ref "C16") (pin "1") (pinfunction "1_1") (pintype "passive"))
      (node (ref "L6") (pin "1") (pinfunction "1_1") (pintype "passive"))
      (node (ref "U$6") (pin "P$2") (pinfunction "P$2_P$2") (pintype "bidirectional"))
    )
    (net (code "28") (name "Net-(C19-Pad1)") (class "Default")
      (node (ref "C19") (pin "1") (pinfunction "1_1") (pintype "passive"))
      (node (ref "L7") (pin "1") (pinfunction "1_1") (pintype "passive"))
      (node (ref "U$7") (pin "P$2") (pinfunction "P$2_P$2") (pintype "bidirectional"))
    )
    (net (code "29") (name "Net-(C22-Pad1)") (class "Default")
      (node (ref "C22") (pin "1") (pinfunction "1_1") (pintype "passive"))
      (node (ref "L8") (pin "1") (pinfunction "1_1") (pintype "passive"))
      (node (ref "U$8") (pin "P$2") (pinfunction "P$2_P$2") (pintype "bidirectional"))
    )
    (net (code "30") (name "Net-(C25-Pad1)") (class "Default")
      (node (ref "C25") (pin "1") (pinfunction "1_1") (pintype "passive"))
      (node (ref "L9") (pin "1") (pinfunction "1_1") (pintype "passive"))
      (node (ref "U$9") (pin "P$2") (pinfunction "P$2_P$2") (pintype "bidirectional"))
    )
    (net (code "31") (name "Net-(C28-Pad1)") (class "Default")
      (node (ref "C28") (pin "1") (pinfunction "1_1") (pintype "passive"))
      (node (ref "L10") (pin "1") (pinfunction "1_1") (pintype "passive"))
      (node (ref "U$10") (pin "P$2") (pinfunction "P$2_P$2") (pintype "bidirectional"))
    )
    (net (code "32") (name "Net-(C31-Pad1)") (class "Default")
      (node (ref "C31") (pin "1") (pinfunction "1_1") (pintype "passive"))
      (node (ref "L11") (pin "1") (pinfunction "1_1") (pintype "passive"))
      (node (ref "U$11") (pin "P$2") (pinfunction "P$2_P$2") (pintype "bidirectional"))
    )
    (net (code "33") (name "Net-(C34-Pad1)") (class "Default")
      (node (ref "C34") (pin "1") (pinfunction "1_1") (pintype "passive"))
      (node (ref "L12") (pin "1") (pinfunction "1_1") (pintype "passive"))
      (node (ref "U$12") (pin "P$2") (pinfunction "P$2_P$2") (pintype "bidirectional"))
    )
    (net (code "34") (name "Net-(C37-Pad1)") (class "Default")
      (node (ref "C37") (pin "1") (pinfunction "1_1") (pintype "passive"))
      (node (ref "L13") (pin "1") (pinfunction "1_1") (pintype "passive"))
      (node (ref "U$13") (pin "P$2") (pinfunction "P$2_P$2") (pintype "bidirectional"))
    )
    (net (code "35") (name "Net-(C40-Pad1)") (class "Default")
      (node (ref "C40") (pin "1") (pinfunction "1_1") (pintype "passive"))
      (node (ref "L14") (pin "1") (pinfunction "1_1") (pintype "passive"))
      (node (ref "U$14") (pin "P$2") (pinfunction "P$2_P$2") (pintype "bidirectional"))
    )
    (net (code "36") (name "Net-(C43-Pad1)") (class "Default")
      (node (ref "C43") (pin "1") (pinfunction "1_1") (pintype "passive"))
      (node (ref "L15") (pin "1") (pinfunction "1_1") (pintype "passive"))
      (node (ref "U$15") (pin "P$2") (pinfunction "P$2_P$2") (pintype "bidirectional"))
    )
    (net (code "37") (name "Net-(C46-Pad1)") (class "Default")
      (node (ref "C46") (pin "1") (pinfunction "1_1") (pintype "passive"))
      (node (ref "L16") (pin "1") (pinfunction "1_1") (pintype "passive"))
      (node (ref "U$16") (pin "P$2") (pinfunction "P$2_P$2") (pintype "bidirectional"))
    )
    (net (code "38") (name "unconnected-(U$17A-P$1-PadP$1A)") (class "Default")
      (node (ref "U$17") (pin "P$1A") (pinfunction "P$1_P$1A") (pintype "bidirectional"))
    )
    (net (code "39") (name "unconnected-(U$17A-P$2-PadP$2A)") (class "Default")
      (node (ref "U$17") (pin "P$2A") (pinfunction "P$2_P$2A") (pintype "bidirectional"))
    )
    (net (code "40") (name "unconnected-(U$17A-P$3-PadP$3A)") (class "Default")
      (node (ref "U$17") (pin "P$3A") (pinfunction "P$3_P$3A") (pintype "bidirectional"))
    )
    (net (code "41") (name "unconnected-(U$17A-P$4-PadP$4A)") (class "Default")
      (node (ref "U$17") (pin "P$4A") (pinfunction "P$4_P$4A") (pintype "bidirectional"))
    )
    (net (code "42") (name "unconnected-(U$17A-P$5-PadP$5A)") (class "Default")
      (node (ref "U$17") (pin "P$5A") (pinfunction "P$5_P$5A") (pintype "bidirectional"))
    )
    (net (code "43") (name "unconnected-(U$17A-P$6-PadP$6A)") (class "Default")
      (node (ref "U$17") (pin "P$6A") (pinfunction "P$6_P$6A") (pintype "bidirectional"))
    )
    (net (code "44") (name "unconnected-(U$17A-P$7-PadP$7A)") (class "Default")
      (node (ref "U$17") (pin "P$7A") (pinfunction "P$7_P$7A") (pintype "bidirectional"))
    )
    (net (code "45") (name "unconnected-(U$17A-P$8-PadP$8A)") (class "Default")
      (node (ref "U$17") (pin "P$8A") (pinfunction "P$8_P$8A") (pintype "bidirectional"))
    )
    (net (code "46") (name "unconnected-(U$17A-P$10-PadP$10A)") (class "Default")
      (node (ref "U$17") (pin "P$10A") (pinfunction "P$10_P$10A") (pintype "bidirectional"))
    )
    (net (code "47") (name "unconnected-(U$17A-P$12-PadP$12A)") (class "Default")
      (node (ref "U$17") (pin "P$12A") (pinfunction "P$12_P$12A") (pintype "bidirectional"))
    )
    (net (code "48") (name "unconnected-(U$17A-P$13-PadP$13A)") (class "Default")
      (node (ref "U$17") (pin "P$13A") (pinfunction "P$13_P$13A") (pintype "bidirectional"))
    )
    (net (code "49") (name "unconnected-(U$17A-P$14-PadP$14A)") (class "Default")
      (node (ref "U$17") (pin "P$14A") (pinfunction "P$14_P$14A") (pintype "bidirectional"))
    )
    (net (code "50") (name "unconnected-(U$17A-P$16-PadP$16A)") (class "Default")
      (node (ref "U$17") (pin "P$16A") (pinfunction "P$16_P$16A") (pintype "bidirectional"))
    )
    (net (code "51") (name "unconnected-(U$17A-P$18-PadP$18A)") (class "Default")
      (node (ref "U$17") (pin "P$18A") (pinfunction "P$18_P$18A") (pintype "bidirectional"))
    )
    (net (code "52") (name "unconnected-(U$17A-P$20-PadP$20A)") (class "Default")
      (node (ref "U$17") (pin "P$20A") (pinfunction "P$20_P$20A") (pintype "bidirectional"))
    )
    (net (code "53") (name "unconnected-(U$17A-P$21-PadP$21A)") (class "Default")
      (node (ref "U$17") (pin "P$21A") (pinfunction "P$21_P$21A") (pintype "bidirectional"))
    )
    (net (code "54") (name "unconnected-(U$17A-P$22-PadP$22A)") (class "Default")
      (node (ref "U$17") (pin "P$22A") (pinfunction "P$22_P$22A") (pintype "bidirectional"))
    )
    (net (code "55") (name "unconnected-(U$17A-P$23-PadP$23A)") (class "Default")
      (node (ref "U$17") (pin "P$23A") (pinfunction "P$23_P$23A") (pintype "bidirectional"))
    )
    (net (code "56") (name "unconnected-(U$17A-P$24-PadP$24A)") (class "Default")
      (node (ref "U$17") (pin "P$24A") (pinfunction "P$24_P$24A") (pintype "bidirectional"))
    )
    (net (code "57") (name "unconnected-(U$17A-P$25-PadP$25A)") (class "Default")
      (node (ref "U$17") (pin "P$25A") (pinfunction "P$25_P$25A") (pintype "bidirectional"))
    )
    (net (code "58") (name "unconnected-(U$17A-P$26-PadP$26A)") (class "Default")
      (node (ref "U$17") (pin "P$26A") (pinfunction "P$26_P$26A") (pintype "bidirectional"))
    )
    (net (code "59") (name "unconnected-(U$17A-P$27-PadP$27A)") (class "Default")
      (node (ref "U$17") (pin "P$27A") (pinfunction "P$27_P$27A") (pintype "bidirectional"))
    )
    (net (code "60") (name "unconnected-(U$17A-P$28-PadP$28A)") (class "Default")
      (node (ref "U$17") (pin "P$28A") (pinfunction "P$28_P$28A") (pintype "bidirectional"))
    )
    (net (code "61") (name "unconnected-(U$17A-P$29-PadP$29A)") (class "Default")
      (node (ref "U$17") (pin "P$29A") (pinfunction "P$29_P$29A") (pintype "bidirectional"))
    )
    (net (code "62") (name "unconnected-(U$17A-P$30-PadP$30A)") (class "Default")
      (node (ref "U$17") (pin "P$30A") (pinfunction "P$30_P$30A") (pintype "bidirectional"))
    )
    (net (code "63") (name "unconnected-(U$17B-P$1-PadP$1A1)") (class "Default")
      (node (ref "U$17") (pin "P$1A1") (pinfunction "P$1_P$1A1") (pintype "bidirectional"))
    )
    (net (code "64") (name "unconnected-(U$17B-P$2-PadP$2A1)") (class "Default")
      (node (ref "U$17") (pin "P$2A1") (pinfunction "P$2_P$2A1") (pintype "bidirectional"))
    )
    (net (code "65") (name "unconnected-(U$17B-P$3-PadP$3A1)") (class "Default")
      (node (ref "U$17") (pin "P$3A1") (pinfunction "P$3_P$3A1") (pintype "bidirectional"))
    )
    (net (code "66") (name "unconnected-(U$17B-P$4-PadP$4A1)") (class "Default")
      (node (ref "U$17") (pin "P$4A1") (pinfunction "P$4_P$4A1") (pintype "bidirectional"))
    )
    (net (code "67") (name "unconnected-(U$17B-P$5-PadP$5A1)") (class "Default")
      (node (ref "U$17") (pin "P$5A1") (pinfunction "P$5_P$5A1") (pintype "bidirectional"))
    )
    (net (code "68") (name "unconnected-(U$17B-P$6-PadP$6A1)") (class "Default")
      (node (ref "U$17") (pin "P$6A1") (pinfunction "P$6_P$6A1") (pintype "bidirectional"))
    )
    (net (code "69") (name "unconnected-(U$17B-P$7-PadP$7A1)") (class "Default")
      (node (ref "U$17") (pin "P$7A1") (pinfunction "P$7_P$7A1") (pintype "bidirectional"))
    )
    (net (code "70") (name "unconnected-(U$17B-P$8-PadP$8A1)") (class "Default")
      (node (ref "U$17") (pin "P$8A1") (pinfunction "P$8_P$8A1") (pintype "bidirectional"))
    )
    (net (code "71") (name "unconnected-(U$17B-P$9-PadP$9A1)") (class "Default")
      (node (ref "U$17") (pin "P$9A1") (pinfunction "P$9_P$9A1") (pintype "bidirectional"))
    )
    (net (code "72") (name "unconnected-(U$17B-P$10-PadP$10A1)") (class "Default")
      (node (ref "U$17") (pin "P$10A1") (pinfunction "P$10_P$10A1") (pintype "bidirectional"))
    )
    (net (code "73") (name "unconnected-(U$17B-P$11-PadP$11A1)") (class "Default")
      (node (ref "U$17") (pin "P$11A1") (pinfunction "P$11_P$11A1") (pintype "bidirectional"))
    )
    (net (code "74") (name "unconnected-(U$17B-P$12-PadP$12A1)") (class "Default")
      (node (ref "U$17") (pin "P$12A1") (pinfunction "P$12_P$12A1") (pintype "bidirectional"))
    )
    (net (code "75") (name "unconnected-(U$17B-P$13-PadP$13A1)") (class "Default")
      (node (ref "U$17") (pin "P$13A1") (pinfunction "P$13_P$13A1") (pintype "bidirectional"))
    )
    (net (code "76") (name "unconnected-(U$17B-P$14-PadP$14A1)") (class "Default")
      (node (ref "U$17") (pin "P$14A1") (pinfunction "P$14_P$14A1") (pintype "bidirectional"))
    )
    (net (code "77") (name "unconnected-(U$17B-P$15-PadP$15A1)") (class "Default")
      (node (ref "U$17") (pin "P$15A1") (pinfunction "P$15_P$15A1") (pintype "bidirectional"))
    )
    (net (code "78") (name "unconnected-(U$17B-P$16-PadP$16A1)") (class "Default")
      (node (ref "U$17") (pin "P$16A1") (pinfunction "P$16_P$16A1") (pintype "bidirectional"))
    )
    (net (code "79") (name "unconnected-(U$17B-P$17-PadP$17A1)") (class "Default")
      (node (ref "U$17") (pin "P$17A1") (pinfunction "P$17_P$17A1") (pintype "bidirectional"))
    )
    (net (code "80") (name "unconnected-(U$17B-P$18-PadP$18A1)") (class "Default")
      (node (ref "U$17") (pin "P$18A1") (pinfunction "P$18_P$18A1") (pintype "bidirectional"))
    )
    (net (code "81") (name "unconnected-(U$17B-P$19-PadP$19A1)") (class "Default")
      (node (ref "U$17") (pin "P$19A1") (pinfunction "P$19_P$19A1") (pintype "bidirectional"))
    )
    (net (code "82") (name "unconnected-(U$17B-P$21-PadP$21A1)") (class "Default")
      (node (ref "U$17") (pin "P$21A1") (pinfunction "P$21_P$21A1") (pintype "bidirectional"))
    )
    (net (code "83") (name "unconnected-(U$17B-P$22-PadP$22A1)") (class "Default")
      (node (ref "U$17") (pin "P$22A1") (pinfunction "P$22_P$22A1") (pintype "bidirectional"))
    )
    (net (code "84") (name "unconnected-(U$17B-P$24-PadP$24A1)") (class "Default")
      (node (ref "U$17") (pin "P$24A1") (pinfunction "P$24_P$24A1") (pintype "bidirectional"))
    )
    (net (code "85") (name "unconnected-(U$17B-P$25-PadP$25A1)") (class "Default")
      (node (ref "U$17") (pin "P$25A1") (pinfunction "P$25_P$25A1") (pintype "bidirectional"))
    )
    (net (code "86") (name "unconnected-(U$17B-P$26-PadP$26A1)") (class "Default")
      (node (ref "U$17") (pin "P$26A1") (pinfunction "P$26_P$26A1") (pintype "bidirectional"))
    )
    (net (code "87") (name "unconnected-(U$17B-P$27-PadP$27A1)") (class "Default")
      (node (ref "U$17") (pin "P$27A1") (pinfunction "P$27_P$27A1") (pintype "bidirectional"))
    )
    (net (code "88") (name "unconnected-(U$17B-P$28-PadP$28A1)") (class "Default")
      (node (ref "U$17") (pin "P$28A1") (pinfunction "P$28_P$28A1") (pintype "bidirectional"))
    )
    (net (code "89") (name "unconnected-(U$17B-P$29-PadP$29A1)") (class "Default")
      (node (ref "U$17") (pin "P$29A1") (pinfunction "P$29_P$29A1") (pintype "bidirectional"))
    )
    (net (code "90") (name "unconnected-(U$17B-P$30-PadP$30A1)") (class "Default")
      (node (ref "U$17") (pin "P$30A1") (pinfunction "P$30_P$30A1") (pintype "bidirectional"))
    )
    (net (code "91") (name "unconnected-(U$17B-P$31-PadP$31A1)") (class "Default")
      (node (ref "U$17") (pin "P$31A1") (pinfunction "P$31_P$31A1") (pintype "bidirectional"))
    )
    (net (code "92") (name "unconnected-(U$17C-P$1-PadP$1A2)") (class "Default")
      (node (ref "U$17") (pin "P$1A2") (pinfunction "P$1_P$1A2") (pintype "bidirectional"))
    )
    (net (code "93") (name "unconnected-(U$17C-P$2-PadP$2A2)") (class "Default")
      (node (ref "U$17") (pin "P$2A2") (pinfunction "P$2_P$2A2") (pintype "bidirectional"))
    )
    (net (code "94") (name "unconnected-(U$17C-P$3-PadP$3A2)") (class "Default")
      (node (ref "U$17") (pin "P$3A2") (pinfunction "P$3_P$3A2") (pintype "bidirectional"))
    )
    (net (code "95") (name "unconnected-(U$17C-P$4-PadP$4A2)") (class "Default")
      (node (ref "U$17") (pin "P$4A2") (pinfunction "P$4_P$4A2") (pintype "bidirectional"))
    )
    (net (code "96") (name "unconnected-(U$17C-P$5-PadP$5A2)") (class "Default")
      (node (ref "U$17") (pin "P$5A2") (pinfunction "P$5_P$5A2") (pintype "bidirectional"))
    )
    (net (code "97") (name "unconnected-(U$17C-P$6-PadP$6A2)") (class "Default")
      (node (ref "U$17") (pin "P$6A2") (pinfunction "P$6_P$6A2") (pintype "bidirectional"))
    )
    (net (code "98") (name "unconnected-(U$17C-P$7-PadP$7A2)") (class "Default")
      (node (ref "U$17") (pin "P$7A2") (pinfunction "P$7_P$7A2") (pintype "bidirectional"))
    )
    (net (code "99") (name "unconnected-(U$17C-P$8-PadP$8A2)") (class "Default")
      (node (ref "U$17") (pin "P$8A2") (pinfunction "P$8_P$8A2") (pintype "bidirectional"))
    )
    (net (code "100") (name "unconnected-(U$17C-P$10-PadP$10A2)") (class "Default")
      (node (ref "U$17") (pin "P$10A2") (pinfunction "P$10_P$10A2") (pintype "bidirectional"))
    )
    (net (code "101") (name "unconnected-(U$17C-P$11-PadP$11A2)") (class "Default")
      (node (ref "U$17") (pin "P$11A2") (pinfunction "P$11_P$11A2") (pintype "bidirectional"))
    )
    (net (code "102") (name "unconnected-(U$17C-P$12-PadP$12A2)") (class "Default")
      (node (ref "U$17") (pin "P$12A2") (pinfunction "P$12_P$12A2") (pintype "bidirectional"))
    )
    (net (code "103") (name "unconnected-(U$17C-P$13-PadP$13A2)") (class "Default")
      (node (ref "U$17") (pin "P$13A2") (pinfunction "P$13_P$13A2") (pintype "bidirectional"))
    )
    (net (code "104") (name "unconnected-(U$17C-P$14-PadP$14A2)") (class "Default")
      (node (ref "U$17") (pin "P$14A2") (pinfunction "P$14_P$14A2") (pintype "bidirectional"))
    )
    (net (code "105") (name "unconnected-(U$17C-P$15-PadP$15A2)") (class "Default")
      (node (ref "U$17") (pin "P$15A2") (pinfunction "P$15_P$15A2") (pintype "bidirectional"))
    )
    (net (code "106") (name "unconnected-(U$17C-P$16-PadP$16A2)") (class "Default")
      (node (ref "U$17") (pin "P$16A2") (pinfunction "P$16_P$16A2") (pintype "bidirectional"))
    )
    (net (code "107") (name "unconnected-(U$17C-P$17-PadP$17A2)") (class "Default")
      (node (ref "U$17") (pin "P$17A2") (pinfunction "P$17_P$17A2") (pintype "bidirectional"))
    )
    (net (code "108") (name "unconnected-(U$17C-P$18-PadP$18A2)") (class "Default")
      (node (ref "U$17") (pin "P$18A2") (pinfunction "P$18_P$18A2") (pintype "bidirectional"))
    )
    (net (code "109") (name "unconnected-(U$17C-P$19-PadP$19A2)") (class "Default")
      (node (ref "U$17") (pin "P$19A2") (pinfunction "P$19_P$19A2") (pintype "bidirectional"))
    )
    (net (code "110") (name "unconnected-(U$17C-P$20-PadP$20A2)") (class "Default")
      (node (ref "U$17") (pin "P$20A2") (pinfunction "P$20_P$20A2") (pintype "bidirectional"))
    )
    (net (code "111") (name "unconnected-(U$17C-P$21-PadP$21A2)") (class "Default")
      (node (ref "U$17") (pin "P$21A2") (pinfunction "P$21_P$21A2") (pintype "bidirectional"))
    )
    (net (code "112") (name "unconnected-(U$17C-P$22-PadP$22A2)") (class "Default")
      (node (ref "U$17") (pin "P$22A2") (pinfunction "P$22_P$22A2") (pintype "bidirectional"))
    )
    (net (code "113") (name "unconnected-(U$17C-P$23-PadP$23A2)") (class "Default")
      (node (ref "U$17") (pin "P$23A2") (pinfunction "P$23_P$23A2") (pintype "bidirectional"))
    )
    (net (code "114") (name "unconnected-(U$17C-P$24-PadP$24A2)") (class "Default")
      (node (ref "U$17") (pin "P$24A2") (pinfunction "P$24_P$24A2") (pintype "bidirectional"))
    )
    (net (code "115") (name "unconnected-(U$17C-P$25-PadP$25A2)") (class "Default")
      (node (ref "U$17") (pin "P$25A2") (pinfunction "P$25_P$25A2") (pintype "bidirectional"))
    )
    (net (code "116") (name "unconnected-(U$17C-P$26-PadP$26A2)") (class "Default")
      (node (ref "U$17") (pin "P$26A2") (pinfunction "P$26_P$26A2") (pintype "bidirectional"))
    )
    (net (code "117") (name "unconnected-(U$17C-P$27-PadP$27A2)") (class "Default")
      (node (ref "U$17") (pin "P$27A2") (pinfunction "P$27_P$27A2") (pintype "bidirectional"))
    )
    (net (code "118") (name "unconnected-(U$17C-P$28-PadP$28A2)") (class "Default")
      (node (ref "U$17") (pin "P$28A2") (pinfunction "P$28_P$28A2") (pintype "bidirectional"))
    )
    (net (code "119") (name "unconnected-(U$17C-P$29-PadP$29A2)") (class "Default")
      (node (ref "U$17") (pin "P$29A2") (pinfunction "P$29_P$29A2") (pintype "bidirectional"))
    )
    (net (code "120") (name "unconnected-(U$17C-P$30-PadP$30A2)") (class "Default")
      (node (ref "U$17") (pin "P$30A2") (pinfunction "P$30_P$30A2") (pintype "bidirectional"))
    )
  )
)
